# FPGA_Configuration.net
KiCad netlist of a schematic drawn in Altium Designer
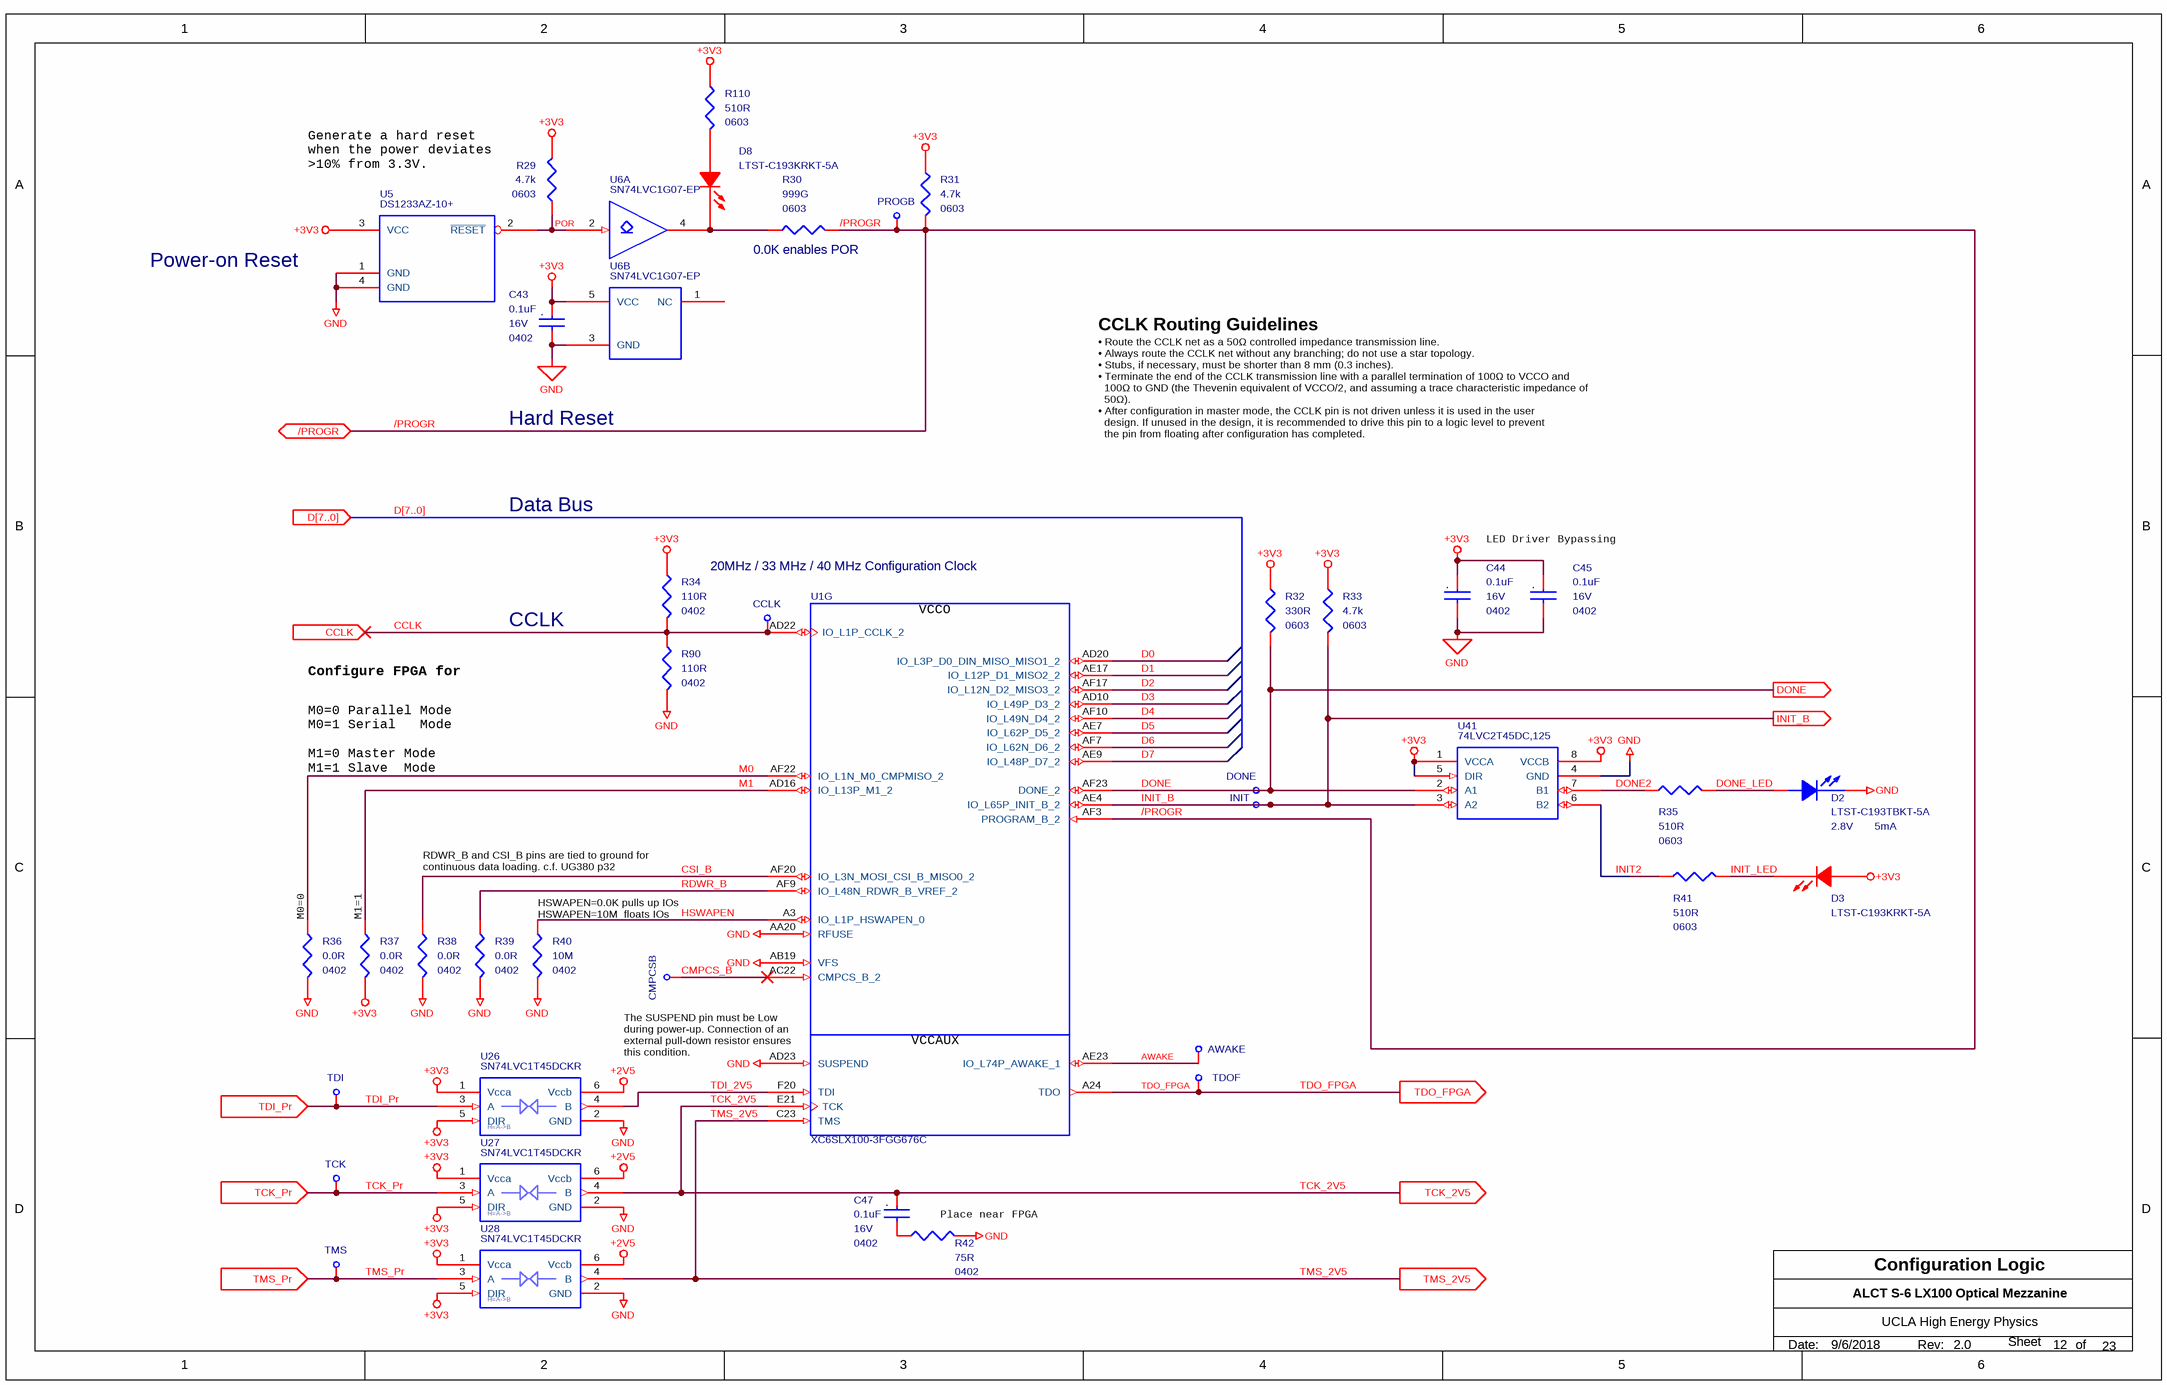
[diagram p0: FPGA_Configuration.SchDoc]

(export (version "E")
  (design (tool "Eeschema 10.0.6"))
  (components
    (comp (ref "AWAKE")
      (value "Test Point Via")
      (footprint "MC_S6/TH/TPVIA")
      (libsource (lib "ALCT_MEZ_SPARTAN6_Library") (part "TPVIA"))
    )
    (comp (ref "C43")
      (value "0.1uF")
      (footprint "MC_S6/SM/C_0402_IPC")
      (description "CAP CER 0.1UF 16V X7R 0402")
      (fields
        (field (name "MANUFACTURER") "KEMET")
        (field (name "MANUFACTURER PART NUMBER") "C0402C104K4RACTU")
        (field (name "PACKAGE") "0402")
        (field (name "VOLTAGE - RATED") "16V")
      )
      (libsource (lib "ALCT_MEZ_SPARTAN6_Library") (part "C0402C104K4RACTU"))
    )
    (comp (ref "C44")
      (value "0.1uF")
      (footprint "MC_S6/SM/C_0402_IPC")
      (description "CAP CER 0.1UF 16V X7R 0402")
      (fields
        (field (name "MANUFACTURER") "KEMET")
        (field (name "MANUFACTURER PART NUMBER") "C0402C104K4RACTU")
        (field (name "PACKAGE") "0402")
        (field (name "VOLTAGE - RATED") "16V")
      )
      (libsource (lib "ALCT_MEZ_SPARTAN6_Library") (part "C0402C104K4RACTU"))
    )
    (comp (ref "C45")
      (value "0.1uF")
      (footprint "MC_S6/SM/C_0402_IPC")
      (description "CAP CER 0.1UF 16V X7R 0402")
      (fields
        (field (name "MANUFACTURER") "KEMET")
        (field (name "MANUFACTURER PART NUMBER") "C0402C104K4RACTU")
        (field (name "PACKAGE") "0402")
        (field (name "VOLTAGE - RATED") "16V")
      )
      (libsource (lib "ALCT_MEZ_SPARTAN6_Library") (part "C0402C104K4RACTU"))
    )
    (comp (ref "C47")
      (value "0.1uF")
      (footprint "MC_S6/SM/C_0402_IPC")
      (description "CAP CER 0.1UF 16V X7R 0402")
      (fields
        (field (name "MANUFACTURER") "KEMET")
        (field (name "MANUFACTURER PART NUMBER") "C0402C104K4RACTU")
        (field (name "PACKAGE") "0402")
        (field (name "VOLTAGE - RATED") "16V")
      )
      (libsource (lib "ALCT_MEZ_SPARTAN6_Library") (part "C0402C104K4RACTU"))
    )
    (comp (ref "CCLK")
      (value "Test Point Via")
      (footprint "MC_S6/TH/TPVIA")
      (libsource (lib "ALCT_MEZ_SPARTAN6_Library") (part "TPVIA"))
    )
    (comp (ref "CMPCSB")
      (value "Test Point Via")
      (footprint "MC_S6/TH/TPVIA")
      (libsource (lib "ALCT_MEZ_SPARTAN6_Library") (part "TPVIA"))
    )
    (comp (ref "D2")
      (value "LTST-C193TBKT-5A")
      (footprint "MC_S6/SM/LED_0603")
      (description "LED BLUE CLEAR 0603 SMD")
      (fields
        (field (name "MANUFACTURER") "Lite-On Inc.")
        (field (name "VOLTAGE - FORWARD (VF) (TYP)") "2.8V")
        (field (name "CURRENT - TEST") "5mA")
      )
      (libsource (lib "ALCT_MEZ_SPARTAN6_Library") (part "LTST-C193TBKT-5A"))
    )
    (comp (ref "D3")
      (value "LTST-C193KRKT-5A")
      (footprint "MC_S6/SM/LED_0603")
      (description "LED RED CLEAR 0603 SMD")
      (fields (field (name "MANUFACTURER") "Lite-On Inc."))
      (libsource (lib "ALCT_MEZ_SPARTAN6_Library") (part "LTST-C193KRKT-5A"))
    )
    (comp (ref "D8")
      (value "LTST-C193KRKT-5A")
      (footprint "MC_S6/SM/LED_0603")
      (description "LED RED CLEAR 0603 SMD")
      (fields (field (name "MANUFACTURER") "Lite-On Inc."))
      (libsource (lib "") (part "LTST-C193KRKT-5A_1"))
    )
    (comp (ref "DONE")
      (value "Test Point Via")
      (footprint "MC_S6/TH/TPVIA")
      (libsource (lib "ALCT_MEZ_SPARTAN6_Library") (part "TPVIA"))
    )
    (comp (ref "INIT")
      (value "Test Point Via")
      (footprint "MC_S6/TH/TPVIA")
      (libsource (lib "") (part "TPVIA_1"))
    )
    (comp (ref "PROGB")
      (value "Test Point Via")
      (footprint "MC_S6/TH/TPVIA")
      (libsource (lib "ALCT_MEZ_SPARTAN6_Library") (part "TPVIA"))
    )
    (comp (ref "R29")
      (value "4.7k")
      (footprint "MC_S6/SM/R_0603_IPC")
      (description "RES SMD 4.7K OHM 1% 1/10W 0603")
      (fields
        (field (name "MANUFACTURER") "Bourns Inc.")
        (field (name "MANUFACTURER PART NUMBER") "CR0603-FX-4701ELF")
        (field (name "SUPPLIER DEVICE PACKAGE") "0603")
      )
      (libsource (lib "ALCT_MEZ_SPARTAN6_Library") (part "CR0603-FX-4701ELF"))
    )
    (comp (ref "R30")
      (value "999G")
      (footprint "MC_S6/SM/R_0603_IPC")
      (description "RES SMD 999G OHM 5% 1/10W 0603")
      (fields
        (field (name "MANUFACTURER PART NUMBER") "Do Not Place")
        (field (name "SUPPLIER DEVICE PACKAGE") "0603")
      )
      (libsource (lib "ALCT_MEZ_SPARTAN6_Library") (part "RES999G 0603"))
    )
    (comp (ref "R31")
      (value "4.7k")
      (footprint "MC_S6/SM/R_0603_IPC")
      (description "RES SMD 4.7K OHM 1% 1/10W 0603")
      (fields
        (field (name "TOLERANCE") "±1%")
        (field (name "MANUFACTURER") "Bourns Inc.")
        (field (name "SUPPLIER DEVICE PACKAGE") "0603")
      )
      (libsource (lib "ALCT_MEZ_SPARTAN6_Library") (part "CR0603-FX-4701ELF"))
    )
    (comp (ref "R32")
      (value "330R")
      (footprint "MC_S6/SM/R_0603_IPC")
      (description "RES SMD 330 OHM 1% 1/10W 0603")
      (fields
        (field (name "TOLERANCE") "±1%")
        (field (name "MANUFACTURER") "Bourns Inc.")
        (field (name "SUPPLIER DEVICE PACKAGE") "0603")
      )
      (libsource (lib "ALCT_MEZ_SPARTAN6_Library") (part "CR0603-FX-3300ELF"))
    )
    (comp (ref "R33")
      (value "4.7k")
      (footprint "MC_S6/SM/R_0603_IPC")
      (description "RES SMD 4.7K OHM 1% 1/10W 0603")
      (fields
        (field (name "TOLERANCE") "±1%")
        (field (name "MANUFACTURER") "Bourns Inc.")
        (field (name "SUPPLIER DEVICE PACKAGE") "0603")
      )
      (libsource (lib "ALCT_MEZ_SPARTAN6_Library") (part "CR0603-FX-4701ELF"))
    )
    (comp (ref "R34")
      (value "110R")
      (footprint "MC_S6/SM/R_0402_IPC")
      (description "RES SMD 110 OHM 1% 1/10W 0402")
      (fields
        (field (name "MANUFACTURER") "Panasonic Electronic Components")
        (field (name "MANUFACTURER PART NUMBER") "ERJ-2RKF1100X")
        (field (name "SUPPLIER DEVICE PACKAGE") "0402")
      )
      (libsource (lib "ALCT_MEZ_SPARTAN6_Library") (part "ERJ-2RKF1100X"))
    )
    (comp (ref "R35")
      (value "510R")
      (footprint "MC_S6/SM/R_0603_IPC")
      (description "RES SMD 510 OHM 1% 1/10W 0603")
      (fields
        (field (name "TOLERANCE") "±1%")
        (field (name "MANUFACTURER") "Bourns Inc.")
        (field (name "SUPPLIER DEVICE PACKAGE") "0603")
      )
      (libsource (lib "ALCT_MEZ_SPARTAN6_Library") (part "CR0603-FX-5100ELF"))
    )
    (comp (ref "R36")
      (value "0.0R")
      (footprint "MC_S6/SM/R_0402_IPC")
      (description "RES SMD 0.0OHM JUMPER 1/10W 0402")
      (fields
        (field (name "TOLERANCE") "Jumper")
        (field (name "MANUFACTURER") "Panasonic Electronic Components")
        (field (name "SUPPLIER DEVICE PACKAGE") "0402")
      )
      (libsource (lib "ALCT_MEZ_SPARTAN6_Library") (part "ERJ-2GE0R00X"))
    )
    (comp (ref "R37")
      (value "0.0R")
      (footprint "MC_S6/SM/R_0402_IPC")
      (description "RES SMD 0.0OHM JUMPER 1/10W 0402")
      (fields
        (field (name "TOLERANCE") "Jumper")
        (field (name "MANUFACTURER") "Panasonic Electronic Components")
        (field (name "SUPPLIER DEVICE PACKAGE") "0402")
      )
      (libsource (lib "ALCT_MEZ_SPARTAN6_Library") (part "ERJ-2GE0R00X"))
    )
    (comp (ref "R38")
      (value "0.0R")
      (footprint "MC_S6/SM/R_0402_IPC")
      (description "RES SMD 0.0OHM JUMPER 1/10W 0402")
      (fields
        (field (name "TOLERANCE") "Jumper")
        (field (name "MANUFACTURER") "Panasonic Electronic Components")
        (field (name "SUPPLIER DEVICE PACKAGE") "0402")
      )
      (libsource (lib "ALCT_MEZ_SPARTAN6_Library") (part "ERJ-2GE0R00X"))
    )
    (comp (ref "R39")
      (value "0.0R")
      (footprint "MC_S6/SM/R_0402_IPC")
      (description "RES SMD 0.0OHM JUMPER 1/10W 0402")
      (fields
        (field (name "TOLERANCE") "Jumper")
        (field (name "MANUFACTURER") "Panasonic Electronic Components")
        (field (name "SUPPLIER DEVICE PACKAGE") "0402")
      )
      (libsource (lib "ALCT_MEZ_SPARTAN6_Library") (part "ERJ-2GE0R00X"))
    )
    (comp (ref "R40")
      (value "10M")
      (footprint "MC_S6/SM/R_0402_IPC")
      (description "RES SMD 10M OHM 5% 1/10W 0402")
      (fields
        (field (name "TOLERANCE") "±5%")
        (field (name "MANUFACTURER") "Panasonic Electronic Components")
        (field (name "SUPPLIER DEVICE PACKAGE") "0402")
      )
      (libsource (lib "ALCT_MEZ_SPARTAN6_Library") (part "ERJ-2GEJ106X"))
    )
    (comp (ref "R41")
      (value "510R")
      (footprint "MC_S6/SM/R_0603_IPC")
      (description "RES SMD 510 OHM 1% 1/10W 0603")
      (fields
        (field (name "TOLERANCE") "±1%")
        (field (name "MANUFACTURER") "Bourns Inc.")
        (field (name "SUPPLIER DEVICE PACKAGE") "0603")
      )
      (libsource (lib "ALCT_MEZ_SPARTAN6_Library") (part "CR0603-FX-5100ELF"))
    )
    (comp (ref "R42")
      (value "75R")
      (footprint "MC_S6/SM/R_0402_IPC")
      (description "RES SMD 75 OHM 5% 1/10W 0402")
      (fields
        (field (name "TOLERANCE") "±5%")
        (field (name "MANUFACTURER") "Panasonic Electronic Components")
        (field (name "SUPPLIER DEVICE PACKAGE") "0402")
      )
      (libsource (lib "ALCT_MEZ_SPARTAN6_Library") (part "ERJ-2GEJ750X"))
    )
    (comp (ref "R90")
      (value "110R")
      (footprint "MC_S6/SM/R_0402_IPC")
      (description "RES SMD 110 OHM 1% 1/10W 0402")
      (fields
        (field (name "MANUFACTURER") "Panasonic Electronic Components")
        (field (name "MANUFACTURER PART NUMBER") "ERJ-2RKF1100X")
        (field (name "SUPPLIER DEVICE PACKAGE") "0402")
      )
      (libsource (lib "ALCT_MEZ_SPARTAN6_Library") (part "ERJ-2RKF1100X"))
    )
    (comp (ref "R110")
      (value "510R")
      (footprint "MC_S6/SM/R_0603_IPC")
      (description "RES SMD 510 OHM 1% 1/10W 0603")
      (fields
        (field (name "TOLERANCE") "±1%")
        (field (name "MANUFACTURER") "Bourns Inc.")
        (field (name "SUPPLIER DEVICE PACKAGE") "0603")
      )
      (libsource (lib "ALCT_MEZ_SPARTAN6_Library") (part "CR0603-FX-5100ELF"))
    )
    (comp (ref "TCK")
      (value "Test Point Via")
      (footprint "MC_S6/TH/TPVIA")
      (libsource (lib "ALCT_MEZ_SPARTAN6_Library") (part "TPVIA"))
    )
    (comp (ref "TDI")
      (value "Test Point Via")
      (footprint "MC_S6/TH/TPVIA")
      (libsource (lib "ALCT_MEZ_SPARTAN6_Library") (part "TPVIA"))
    )
    (comp (ref "TDOF")
      (value "Test Point Via")
      (footprint "MC_S6/TH/TPVIA")
      (libsource (lib "ALCT_MEZ_SPARTAN6_Library") (part "TPVIA"))
    )
    (comp (ref "TMS")
      (value "Test Point Via")
      (footprint "MC_S6/TH/TPVIA")
      (libsource (lib "ALCT_MEZ_SPARTAN6_Library") (part "TPVIA"))
    )
    (comp (ref "U1")
      (value "XC6SLX100-3FGG676C")
      (footprint "FGG676")
      (fields (field (name "MANUFACTURER") "Xilinx Inc."))
      (libsource (lib "ALCT_MEZ_SPARTAN6_Library") (part "XC6SLX100-3FGG676C"))
    )
    (comp (ref "U5")
      (value "DS1233AZ-10+")
      (footprint "MC_S6/SM/SOT223_1243")
      (description "IC POR 2.88V 10% SOT223")
      (fields
        (field (name "MANUFACTURER") "Maxim Integrated")
        (field (name "MANUFACTURER PART NUMBER") "DS1233AZ-10+T&R")
      )
      (libsource (lib "ALCT_MEZ_SPARTAN6_Library") (part "DS1233AZ-10+"))
    )
    (comp (ref "U6")
      (value "SN74LVC1G07-EP")
      (footprint "SOT353-1")
      (description "IC BUFF/DVR NON-INVERT Open Drain SC70-5")
      (fields
        (field (name "MANUFACTURER") "Texas Instruments")
        (field (name "MANUFACTURER PART NUMBER") "SN74LVC1G07MDCKREP")
      )
      (libsource (lib "ALCT_MEZ_SPARTAN6_Library") (part "SN74LVC1G07-EP"))
    )
    (comp (ref "U26")
      (value "SN74LVC1T45DCKR")
      (footprint "MC_S6/SM/SOT_SC70_DCK6")
      (description "IC BUS TRANSCVR TRI-ST SC70-6")
      (fields (field (name "MANUFACTURER") "Texas Instruments"))
      (libsource (lib "ALCT_MEZ_SPARTAN6_Library") (part "SN74LVC1T45-EP-ALCT_1"))
    )
    (comp (ref "U27")
      (value "SN74LVC1T45DCKR")
      (footprint "MC_S6/SM/SOT_SC70_DCK6")
      (description "IC BUS TRANSCVR TRI-ST SC70-6")
      (fields (field (name "MANUFACTURER") "Texas Instruments"))
      (libsource (lib "ALCT_MEZ_SPARTAN6_Library") (part "SN74LVC1T45-EP-ALCT_1"))
    )
    (comp (ref "U28")
      (value "SN74LVC1T45DCKR")
      (footprint "MC_S6/SM/SOT_SC70_DCK6")
      (description "IC BUS TRANSCVR TRI-ST SC70-6")
      (fields (field (name "MANUFACTURER") "Texas Instruments"))
      (libsource (lib "ALCT_MEZ_SPARTAN6_Library") (part "SN74LVC1T45-EP-ALCT_1"))
    )
    (comp (ref "U41")
      (value "74LVC2T45DC,125")
      (footprint "VSSOP8 SOT765-1")
      (description "IC TRNSLTR BIDIRECTIONAL 8VSSOP")
      (fields (field (name "MANUFACTURER") "Nexperia USA Inc.") (field (name "BASE PART NUMBER") "74LVC2T45"))
      (libsource (lib "ALCT_MEZ_SPARTAN6_Library") (part "74LVC2T45DC,125"))
    )
  )
  (nets
    (net (code "1") (name "+2V5") (class "Default")
      (node (ref "U26") (pin "6") (pinfunction "Vccb_6") (pintype "power_in"))
      (node (ref "U27") (pin "6") (pinfunction "Vccb_6") (pintype "power_in"))
      (node (ref "U28") (pin "6") (pinfunction "Vccb_6") (pintype "power_in"))
    )
    (net (code "2") (name "+3V3") (class "Default")
      (node (ref "C43") (pin "1") (pinfunction "1_1") (pintype "passive"))
      (node (ref "C44") (pin "1") (pinfunction "1_1") (pintype "passive"))
      (node (ref "C45") (pin "1") (pinfunction "1_1") (pintype "passive"))
      (node (ref "D3") (pin "A") (pinfunction "ANODE_A") (pintype "passive"))
      (node (ref "R110") (pin "1") (pinfunction "1_1") (pintype "passive"))
      (node (ref "R29") (pin "1") (pinfunction "1_1") (pintype "passive"))
      (node (ref "R31") (pin "1") (pinfunction "1_1") (pintype "passive"))
      (node (ref "R32") (pin "1") (pinfunction "1_1") (pintype "passive"))
      (node (ref "R33") (pin "1") (pinfunction "1_1") (pintype "passive"))
      (node (ref "R34") (pin "1") (pinfunction "1_1") (pintype "passive"))
      (node (ref "R37") (pin "2") (pinfunction "2_2") (pintype "passive"))
      (node (ref "U26") (pin "1") (pinfunction "Vcca_1") (pintype "power_in"))
      (node (ref "U26") (pin "5") (pinfunction "DIR_5") (pintype "input"))
      (node (ref "U27") (pin "1") (pinfunction "Vcca_1") (pintype "power_in"))
      (node (ref "U27") (pin "5") (pinfunction "DIR_5") (pintype "input"))
      (node (ref "U28") (pin "1") (pinfunction "Vcca_1") (pintype "power_in"))
      (node (ref "U28") (pin "5") (pinfunction "DIR_5") (pintype "input"))
      (node (ref "U41") (pin "1") (pinfunction "VCCA_1") (pintype "power_in"))
      (node (ref "U41") (pin "5") (pinfunction "DIR_5") (pintype "input"))
      (node (ref "U41") (pin "8") (pinfunction "VCCB_8") (pintype "passive"))
      (node (ref "U5") (pin "3") (pinfunction "VCC_3") (pintype "power_in"))
      (node (ref "U6") (pin "5") (pinfunction "VCC_5") (pintype "power_in"))
    )
    (net (code "3") (name "/AWAKE") (class "Default")
      (node (ref "AWAKE") (pin "1") (pinfunction "In_1") (pintype "passive"))
      (node (ref "U1") (pin "AE23") (pinfunction "IO_L74P_AWAKE_1_AE23") (pintype "bidirectional"))
    )
    (net (code "4") (name "/CCLK") (class "Default")
      (node (ref "CCLK") (pin "1") (pinfunction "In_1") (pintype "passive"))
      (node (ref "R34") (pin "2") (pinfunction "2_2") (pintype "passive"))
      (node (ref "R90") (pin "1") (pinfunction "1_1") (pintype "passive"))
      (node (ref "U1") (pin "AD22") (pinfunction "IO_L1P_CCLK_2_AD22") (pintype "bidirectional"))
    )
    (net (code "5") (name "/CMPCS_B") (class "Default")
      (node (ref "CMPCSB") (pin "1") (pinfunction "In_1") (pintype "passive"))
      (node (ref "U1") (pin "AC22") (pinfunction "CMPCS_B_2_AC22") (pintype "input"))
    )
    (net (code "6") (name "/CSI_B") (class "Default")
      (node (ref "R38") (pin "1") (pinfunction "1_1") (pintype "passive"))
      (node (ref "U1") (pin "AF20") (pinfunction "IO_L3N_MOSI_CSI_B_MISO0_2_AF20") (pintype "bidirectional"))
    )
    (net (code "7") (name "/D0") (class "Default")
      (node (ref "U1") (pin "AD20") (pinfunction "IO_L3P_D0_DIN_MISO_MISO1_2_AD20") (pintype "bidirectional"))
    )
    (net (code "8") (name "/D1") (class "Default")
      (node (ref "U1") (pin "AE17") (pinfunction "IO_L12P_D1_MISO2_2_AE17") (pintype "bidirectional"))
    )
    (net (code "9") (name "/D2") (class "Default")
      (node (ref "U1") (pin "AF17") (pinfunction "IO_L12N_D2_MISO3_2_AF17") (pintype "bidirectional"))
    )
    (net (code "10") (name "/D3") (class "Default")
      (node (ref "U1") (pin "AD10") (pinfunction "IO_L49P_D3_2_AD10") (pintype "bidirectional"))
    )
    (net (code "11") (name "/D4") (class "Default")
      (node (ref "U1") (pin "AF10") (pinfunction "IO_L49N_D4_2_AF10") (pintype "bidirectional"))
    )
    (net (code "12") (name "/D5") (class "Default")
      (node (ref "U1") (pin "AE7") (pinfunction "IO_L62P_D5_2_AE7") (pintype "bidirectional"))
    )
    (net (code "13") (name "/D6") (class "Default")
      (node (ref "U1") (pin "AF7") (pinfunction "IO_L62N_D6_2_AF7") (pintype "bidirectional"))
    )
    (net (code "14") (name "/D7") (class "Default")
      (node (ref "U1") (pin "AE9") (pinfunction "IO_L48P_D7_2_AE9") (pintype "bidirectional"))
    )
    (net (code "15") (name "/DONE") (class "Default")
      (node (ref "DONE") (pin "1") (pinfunction "In_1") (pintype "passive"))
      (node (ref "R32") (pin "2") (pinfunction "2_2") (pintype "passive"))
      (node (ref "U1") (pin "AF23") (pinfunction "DONE_2_AF23") (pintype "bidirectional"))
      (node (ref "U41") (pin "2") (pinfunction "A1_2") (pintype "bidirectional"))
    )
    (net (code "16") (name "/DONE2") (class "Default")
      (node (ref "R35") (pin "1") (pinfunction "1_1") (pintype "passive"))
      (node (ref "U41") (pin "7") (pinfunction "B1_7") (pintype "bidirectional"))
    )
    (net (code "17") (name "/DONE_LED") (class "Default")
      (node (ref "D2") (pin "A") (pinfunction "ANODE_A") (pintype "passive"))
      (node (ref "R35") (pin "2") (pinfunction "2_2") (pintype "passive"))
    )
    (net (code "19") (name "/HSWAPEN") (class "Default")
      (node (ref "R40") (pin "1") (pinfunction "1_1") (pintype "passive"))
      (node (ref "U1") (pin "A3") (pinfunction "IO_L1P_HSWAPEN_0_A3") (pintype "bidirectional"))
    )
    (net (code "20") (name "/INIT2") (class "Default")
      (node (ref "R41") (pin "1") (pinfunction "1_1") (pintype "passive"))
      (node (ref "U41") (pin "6") (pinfunction "B2_6") (pintype "bidirectional"))
    )
    (net (code "21") (name "/INIT_B") (class "Default")
      (node (ref "INIT") (pin "1") (pinfunction "In_1") (pintype "passive"))
      (node (ref "R33") (pin "2") (pinfunction "2_2") (pintype "passive"))
      (node (ref "U1") (pin "AE4") (pinfunction "IO_L65P_INIT_B_2_AE4") (pintype "bidirectional"))
      (node (ref "U41") (pin "3") (pinfunction "A2_3") (pintype "bidirectional"))
    )
    (net (code "22") (name "/INIT_LED") (class "Default")
      (node (ref "D3") (pin "K") (pinfunction "CATHODE_K") (pintype "passive"))
      (node (ref "R41") (pin "2") (pinfunction "2_2") (pintype "passive"))
    )
    (net (code "23") (name "/M0") (class "Default")
      (node (ref "R36") (pin "1") (pinfunction "1_1") (pintype "passive"))
      (node (ref "U1") (pin "AF22") (pinfunction "IO_L1N_M0_CMPMISO_2_AF22") (pintype "bidirectional"))
    )
    (net (code "24") (name "/M1") (class "Default")
      (node (ref "R37") (pin "1") (pinfunction "1_1") (pintype "passive"))
      (node (ref "U1") (pin "AD16") (pinfunction "IO_L13P_M1_2_AD16") (pintype "bidirectional"))
    )
    (net (code "25") (name "/POR") (class "Default")
      (node (ref "R29") (pin "2") (pinfunction "2_2") (pintype "passive"))
      (node (ref "U5") (pin "2") (pinfunction "~{RESET}_2") (pintype "open_collector"))
      (node (ref "U6") (pin "2") (pinfunction "A_2") (pintype "input"))
    )
    (net (code "26") (name "/RDWR_B") (class "Default")
      (node (ref "R39") (pin "1") (pinfunction "1_1") (pintype "passive"))
      (node (ref "U1") (pin "AF9") (pinfunction "IO_L48N_RDWR_B_VREF_2_AF9") (pintype "bidirectional"))
    )
    (net (code "27") (name "/TCK_2V5") (class "Default")
      (node (ref "C47") (pin "1") (pinfunction "1_1") (pintype "passive"))
      (node (ref "U1") (pin "E21") (pinfunction "TCK_E21") (pintype "input"))
      (node (ref "U27") (pin "4") (pinfunction "B_4") (pintype "output"))
    )
    (net (code "28") (name "/TCK_Pr") (class "Default")
      (node (ref "TCK") (pin "1") (pinfunction "In_1") (pintype "passive"))
      (node (ref "U27") (pin "3") (pinfunction "A_3") (pintype "input"))
    )
    (net (code "29") (name "/TDI_2V5") (class "Default")
      (node (ref "U1") (pin "F20") (pinfunction "TDI_F20") (pintype "input"))
      (node (ref "U26") (pin "4") (pinfunction "B_4") (pintype "output"))
    )
    (net (code "30") (name "/TDI_Pr") (class "Default")
      (node (ref "TDI") (pin "1") (pinfunction "In_1") (pintype "passive"))
      (node (ref "U26") (pin "3") (pinfunction "A_3") (pintype "input"))
    )
    (net (code "31") (name "/TDO_FPGA") (class "Default")
      (node (ref "TDOF") (pin "1") (pinfunction "In_1") (pintype "passive"))
      (node (ref "U1") (pin "A24") (pinfunction "TDO_A24") (pintype "output"))
    )
    (net (code "32") (name "/TMS_2V5") (class "Default")
      (node (ref "U1") (pin "C23") (pinfunction "TMS_C23") (pintype "input"))
      (node (ref "U28") (pin "4") (pinfunction "B_4") (pintype "output"))
    )
    (net (code "33") (name "/TMS_Pr") (class "Default")
      (node (ref "TMS") (pin "1") (pinfunction "In_1") (pintype "passive"))
      (node (ref "U28") (pin "3") (pinfunction "A_3") (pintype "input"))
    )
    (net (code "34") (name "/{slash}PROGR") (class "Default")
      (node (ref "PROGB") (pin "1") (pinfunction "In_1") (pintype "passive"))
      (node (ref "R30") (pin "2") (pinfunction "2_2") (pintype "passive"))
      (node (ref "R31") (pin "2") (pinfunction "2_2") (pintype "passive"))
      (node (ref "U1") (pin "AF3") (pinfunction "PROGRAM_B_2_AF3") (pintype "input"))
    )
    (net (code "35") (name "GND") (class "Default")
      (node (ref "C43") (pin "2") (pinfunction "2_2") (pintype "passive"))
      (node (ref "C44") (pin "2") (pinfunction "2_2") (pintype "passive"))
      (node (ref "C45") (pin "2") (pinfunction "2_2") (pintype "passive"))
      (node (ref "D2") (pin "K") (pinfunction "CATHODE_K") (pintype "passive"))
      (node (ref "R36") (pin "2") (pinfunction "2_2") (pintype "passive"))
      (node (ref "R38") (pin "2") (pinfunction "2_2") (pintype "passive"))
      (node (ref "R39") (pin "2") (pinfunction "2_2") (pintype "passive"))
      (node (ref "R40") (pin "2") (pinfunction "2_2") (pintype "passive"))
      (node (ref "R42") (pin "2") (pinfunction "2_2") (pintype "passive"))
      (node (ref "R90") (pin "2") (pinfunction "2_2") (pintype "passive"))
      (node (ref "U1") (pin "AA20") (pinfunction "RFUSE_AA20") (pintype "input"))
      (node (ref "U1") (pin "AB19") (pinfunction "VFS_AB19") (pintype "input"))
      (node (ref "U1") (pin "AD23") (pinfunction "SUSPEND_AD23") (pintype "input"))
      (node (ref "U26") (pin "2") (pinfunction "GND_2") (pintype "power_in"))
      (node (ref "U27") (pin "2") (pinfunction "GND_2") (pintype "power_in"))
      (node (ref "U28") (pin "2") (pinfunction "GND_2") (pintype "power_in"))
      (node (ref "U41") (pin "4") (pinfunction "GND_4") (pintype "power_in"))
      (node (ref "U5") (pin "1") (pinfunction "GND_1") (pintype "power_in"))
      (node (ref "U5") (pin "4") (pinfunction "GND_4") (pintype "power_in"))
      (node (ref "U6") (pin "3") (pinfunction "GND_3") (pintype "power_in"))
    )
    (net (code "36") (name "Net-(C47-Pad2)") (class "Default")
      (node (ref "C47") (pin "2") (pinfunction "2_2") (pintype "passive"))
      (node (ref "R42") (pin "1") (pinfunction "1_1") (pintype "passive"))
    )
    (net (code "37") (name "Net-(D8-ANODE)") (class "Default")
      (node (ref "D8") (pin "A") (pinfunction "ANODE_A") (pintype "passive"))
      (node (ref "R110") (pin "2") (pinfunction "2_2") (pintype "passive"))
    )
    (net (code "38") (name "Net-(D8-CATHODE)") (class "Default")
      (node (ref "D8") (pin "K") (pinfunction "CATHODE_K") (pintype "passive"))
      (node (ref "R30") (pin "1") (pinfunction "1_1") (pintype "passive"))
      (node (ref "U6") (pin "4") (pinfunction "Y_4") (pintype "open_collector"))
    )
    (net (code "39") (name "unconnected-(U6B-NC-Pad1)") (class "Default")
      (node (ref "U6") (pin "1") (pinfunction "NC_1") (pintype "passive"))
    )
  )
)
